# transistorboard.net
KiCad netlist of a schematic drawn in EAGLE
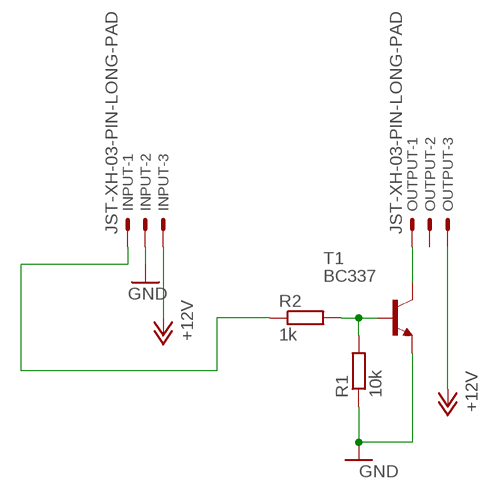
[diagram p0: schematic, sheet 1]

(export (version "E")
  (design (tool "Eeschema 10.0.6"))
  (components
    (comp (ref "INPUT")
      (value "JST-XH-03-PIN-LONG-PAD")
      (footprint "eagle-import:JST-XH-03-PACKAGE-LONG-PAD")
      (libsource (lib "eagle-import") (part "JST-XH-03-PIN-LONG-PAD"))
    )
    (comp (ref "OUTPUT")
      (value "JST-XH-03-PIN-LONG-PAD")
      (footprint "eagle-import:JST-XH-03-PACKAGE-LONG-PAD")
      (libsource (lib "eagle-import") (part "JST-XH-03-PIN-LONG-PAD"))
    )
    (comp (ref "R1")
      (value "10k")
      (footprint "eagle-import:0204_7")
      (libsource (lib "eagle-import") (part "R-EU_0204/7"))
    )
    (comp (ref "R2")
      (value "1k")
      (footprint "eagle-import:0204_7")
      (libsource (lib "eagle-import") (part "R-EU_0204/7"))
    )
    (comp (ref "T1")
      (value "BC337")
      (footprint "eagle-import:TO92")
      (libsource (lib "eagle-import") (part "BC337"))
    )
  )
  (nets
    (net (code "1") (name "+12V") (class "Default")
      (node (ref "INPUT") (pin "3") (pinfunction "S_3") (pintype "passive"))
      (node (ref "OUTPUT") (pin "3") (pinfunction "S_3") (pintype "passive"))
    )
    (net (code "2") (name "GND") (class "Default")
      (node (ref "INPUT") (pin "2") (pinfunction "S_2") (pintype "passive"))
      (node (ref "R1") (pin "1") (pinfunction "1_1") (pintype "passive"))
      (node (ref "T1") (pin "1") (pinfunction "E_1") (pintype "passive"))
    )
    (net (code "3") (name "Net-(INPUTA-S)") (class "Default")
      (node (ref "INPUT") (pin "1") (pinfunction "S_1") (pintype "passive"))
      (node (ref "R2") (pin "1") (pinfunction "1_1") (pintype "passive"))
    )
    (net (code "4") (name "Net-(OUTPUTA-S)") (class "Default")
      (node (ref "OUTPUT") (pin "1") (pinfunction "S_1") (pintype "passive"))
      (node (ref "T1") (pin "3") (pinfunction "C_3") (pintype "passive"))
    )
    (net (code "5") (name "Net-(T1-B)") (class "Default")
      (node (ref "R1") (pin "2") (pinfunction "2_2") (pintype "passive"))
      (node (ref "R2") (pin "2") (pinfunction "2_2") (pintype "passive"))
      (node (ref "T1") (pin "2") (pinfunction "B_2") (pintype "passive"))
    )
    (net (code "6") (name "unconnected-(OUTPUTB-S-Pad2)") (class "Default")
      (node (ref "OUTPUT") (pin "2") (pinfunction "S_2") (pintype "passive"))
    )
  )
)
